# Monostable_Clock.net
KiCad netlist of a schematic drawn in Altium Designer
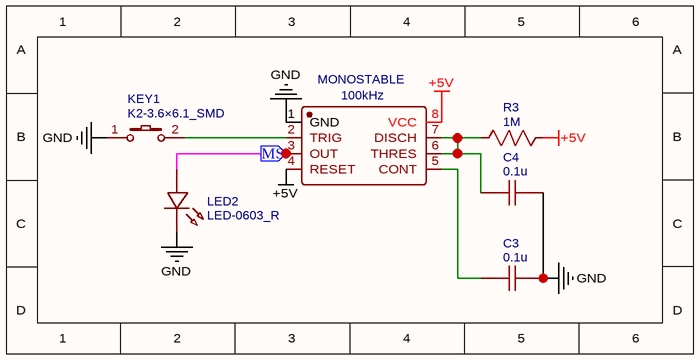
[diagram p0: Monostable Clock.schdoc]

(export (version "E")
  (design (tool "Eeschema 10.0.6"))
  (components
    (comp (ref "C3")
      (value "0.1u")
      (fields (field (name "CONTRIBUTOR") "LCEDA_Lib"))
      (libsource (lib "altium-import") (part "root_0_0.1u_"))
    )
    (comp (ref "C4")
      (value "0.1u")
      (fields (field (name "CONTRIBUTOR") "LCEDA_Lib"))
      (libsource (lib "altium-import") (part "root_0_0.1u_"))
    )
    (comp (ref "KEY1")
      (value "K2-3.6×6.1_SMD")
      (fields (field (name "MANUFACTURER PART") "K2-1107ST-A4SW-06") (field (name "CONTRIBUTOR") "LCEDA_Lib"))
      (libsource (lib "altium-import") (part "root_0_K2-3.6×6.1_SMD_"))
    )
    (comp (ref "LED2")
      (value "LED-0603_R")
      (fields
        (field (name "MANUFACTURER") "EVERLIGHT(台湾亿光)")
        (field (name "MANUFACTURER PART") "19-217/R6C-AL1M2VY/3T")
        (field (name "CONTRIBUTOR") "LCEDA_01")
      )
      (libsource (lib "altium-import") (part "root_3_LED-0603_R_"))
    )
    (comp (ref "MONOSTABLE")
      (value "100kHz")
      (fields
        (field (name "MANUFACTURER") "TI(德州仪器)")
        (field (name "MANUFACTURER PART") "NE555PSRE4")
        (field (name "CONTRIBUTOR") "lcsc")
      )
      (libsource (lib "altium-import") (part "root_0_100kHz_"))
    )
    (comp (ref "R3")
      (value "1M")
      (fields (field (name "CONTRIBUTOR") "LCEDA_Lib"))
      (libsource (lib "altium-import") (part "root_0_1M_"))
    )
  )
  (nets
    (net (code "1") (name "+5V") (class "Default")
      (node (ref "MONOSTABLE") (pin "4") (pinfunction "RESET_4") (pintype "passive"))
      (node (ref "MONOSTABLE") (pin "8") (pinfunction "VCC_8") (pintype "passive"))
      (node (ref "R3") (pin "2") (pinfunction "2_2") (pintype "passive"))
    )
    (net (code "2") (name "/MS") (class "Default")
      (node (ref "LED2") (pin "1") (pinfunction "1_1") (pintype "passive"))
      (node (ref "MONOSTABLE") (pin "3") (pinfunction "OUT_3") (pintype "passive"))
    )
    (net (code "3") (name "GND") (class "Default")
      (node (ref "C3") (pin "2") (pinfunction "2_2") (pintype "passive"))
      (node (ref "C4") (pin "2") (pinfunction "2_2") (pintype "passive"))
      (node (ref "KEY1") (pin "1") (pinfunction "1_1") (pintype "passive"))
      (node (ref "LED2") (pin "2") (pinfunction "2_2") (pintype "passive"))
      (node (ref "MONOSTABLE") (pin "1") (pinfunction "GND_1") (pintype "passive"))
    )
    (net (code "4") (name "Net-(MONOSTABLE-CONT)") (class "Default")
      (node (ref "C3") (pin "1") (pinfunction "1_1") (pintype "passive"))
      (node (ref "MONOSTABLE") (pin "5") (pinfunction "CONT_5") (pintype "passive"))
    )
    (net (code "5") (name "Net-(MONOSTABLE-DISCH)") (class "Default")
      (node (ref "C4") (pin "1") (pinfunction "1_1") (pintype "passive"))
      (node (ref "MONOSTABLE") (pin "6") (pinfunction "THRES_6") (pintype "passive"))
      (node (ref "MONOSTABLE") (pin "7") (pinfunction "DISCH_7") (pintype "passive"))
      (node (ref "R3") (pin "1") (pinfunction "1_1") (pintype "passive"))
    )
    (net (code "6") (name "Net-(MONOSTABLE-TRIG)") (class "Default")
      (node (ref "KEY1") (pin "2") (pinfunction "2_2") (pintype "passive"))
      (node (ref "MONOSTABLE") (pin "2") (pinfunction "TRIG_2") (pintype "passive"))
    )
  )
)
